# USBSocket_Type5_v1_0.net
KiCad netlist of a schematic drawn in EAGLE
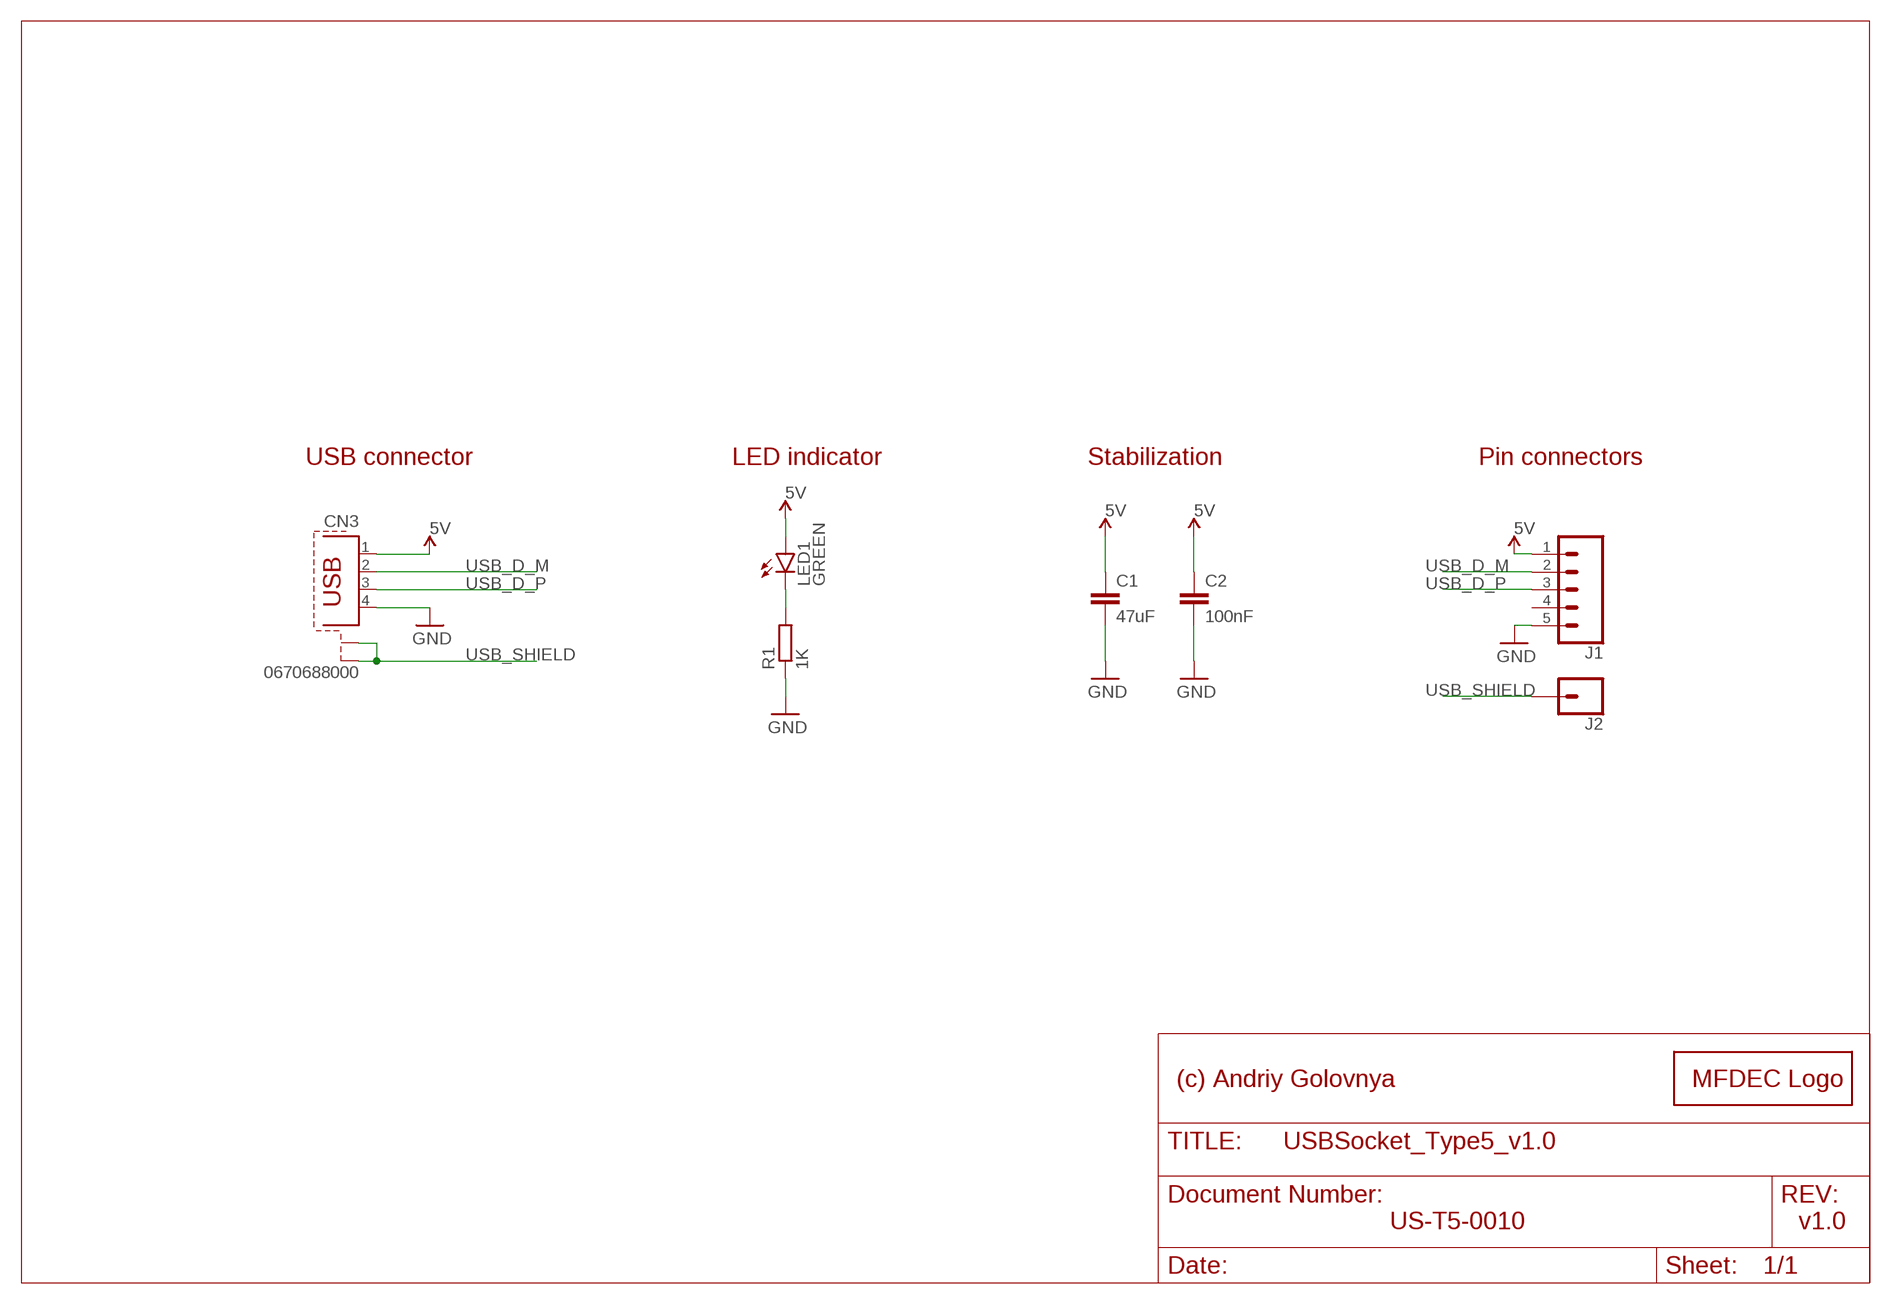
[diagram p0: schematic, sheet 1]

(export (version "E")
  (design (tool "Eeschema 10.0.6"))
  (components
    (comp (ref "C1")
      (value "47uF")
      (footprint "eagle-import:C0805")
      (libsource (lib "eagle-import") (part "C-EUC0805"))
    )
    (comp (ref "C2")
      (value "100nF")
      (footprint "eagle-import:C0402")
      (libsource (lib "eagle-import") (part "C-EUC0402"))
    )
    (comp (ref "CN3")
      (value "0670688000")
      (footprint "eagle-import:PN61729-S")
      (libsource (lib "eagle-import") (part "PN61729-S"))
    )
    (comp (ref "J1")
      (value "CONN_05PTH")
      (footprint "eagle-import:1X05")
      (libsource (lib "eagle-import") (part "CONN_05PTH"))
    )
    (comp (ref "J2")
      (value "CONN_01")
      (footprint "eagle-import:1X01")
      (libsource (lib "eagle-import") (part "CONN_01"))
    )
    (comp (ref "LED1")
      (value "GREEN")
      (footprint "eagle-import:SML0603")
      (libsource (lib "eagle-import") (part "LEDSML0603"))
    )
    (comp (ref "LOGO1")
      (value "MFDECLOGO_L_10MM")
      (footprint "eagle-import:MFDEC_L_10MM")
      (libsource (lib "eagle-import") (part "MFDECLOGO_L_10MM"))
    )
    (comp (ref "R1")
      (value "1K")
      (footprint "eagle-import:R0402")
      (libsource (lib "eagle-import") (part "R-EU_R0402"))
    )
  )
  (nets
    (net (code "1") (name "/USB_D_M") (class "Default")
      (node (ref "CN3") (pin "2") (pinfunction "2_2") (pintype "passive"))
      (node (ref "J1") (pin "2") (pinfunction "2_2") (pintype "passive"))
    )
    (net (code "2") (name "/USB_D_P") (class "Default")
      (node (ref "CN3") (pin "3") (pinfunction "3_3") (pintype "passive"))
      (node (ref "J1") (pin "3") (pinfunction "3_3") (pintype "passive"))
    )
    (net (code "3") (name "/USB_SHIELD") (class "Default")
      (node (ref "CN3") (pin "S1") (pinfunction "S1_S1") (pintype "passive"))
      (node (ref "CN3") (pin "S2") (pinfunction "S2_S2") (pintype "passive"))
      (node (ref "J2") (pin "1") (pinfunction "1_1") (pintype "passive"))
    )
    (net (code "4") (name "5V") (class "Default")
      (node (ref "C1") (pin "1") (pinfunction "1_1") (pintype "passive"))
      (node (ref "C2") (pin "1") (pinfunction "1_1") (pintype "passive"))
      (node (ref "CN3") (pin "1") (pinfunction "1_1") (pintype "passive"))
      (node (ref "J1") (pin "1") (pinfunction "1_1") (pintype "passive"))
      (node (ref "LED1") (pin "A") (pinfunction "A_A") (pintype "passive"))
    )
    (net (code "5") (name "GND") (class "Default")
      (node (ref "C1") (pin "2") (pinfunction "2_2") (pintype "passive"))
      (node (ref "C2") (pin "2") (pinfunction "2_2") (pintype "passive"))
      (node (ref "CN3") (pin "4") (pinfunction "4_4") (pintype "passive"))
      (node (ref "J1") (pin "5") (pinfunction "5_5") (pintype "passive"))
      (node (ref "R1") (pin "1") (pinfunction "1_1") (pintype "passive"))
    )
    (net (code "6") (name "Net-(LED1-PadC)") (class "Default")
      (node (ref "LED1") (pin "C") (pinfunction "C_C") (pintype "passive"))
      (node (ref "R1") (pin "2") (pinfunction "2_2") (pintype "passive"))
    )
    (net (code "7") (name "unconnected-(J1-Pad4)") (class "Default")
      (node (ref "J1") (pin "4") (pinfunction "4_4") (pintype "passive"))
    )
  )
)
